# Sheet1.net
KiCad netlist of a schematic drawn in Altium Designer
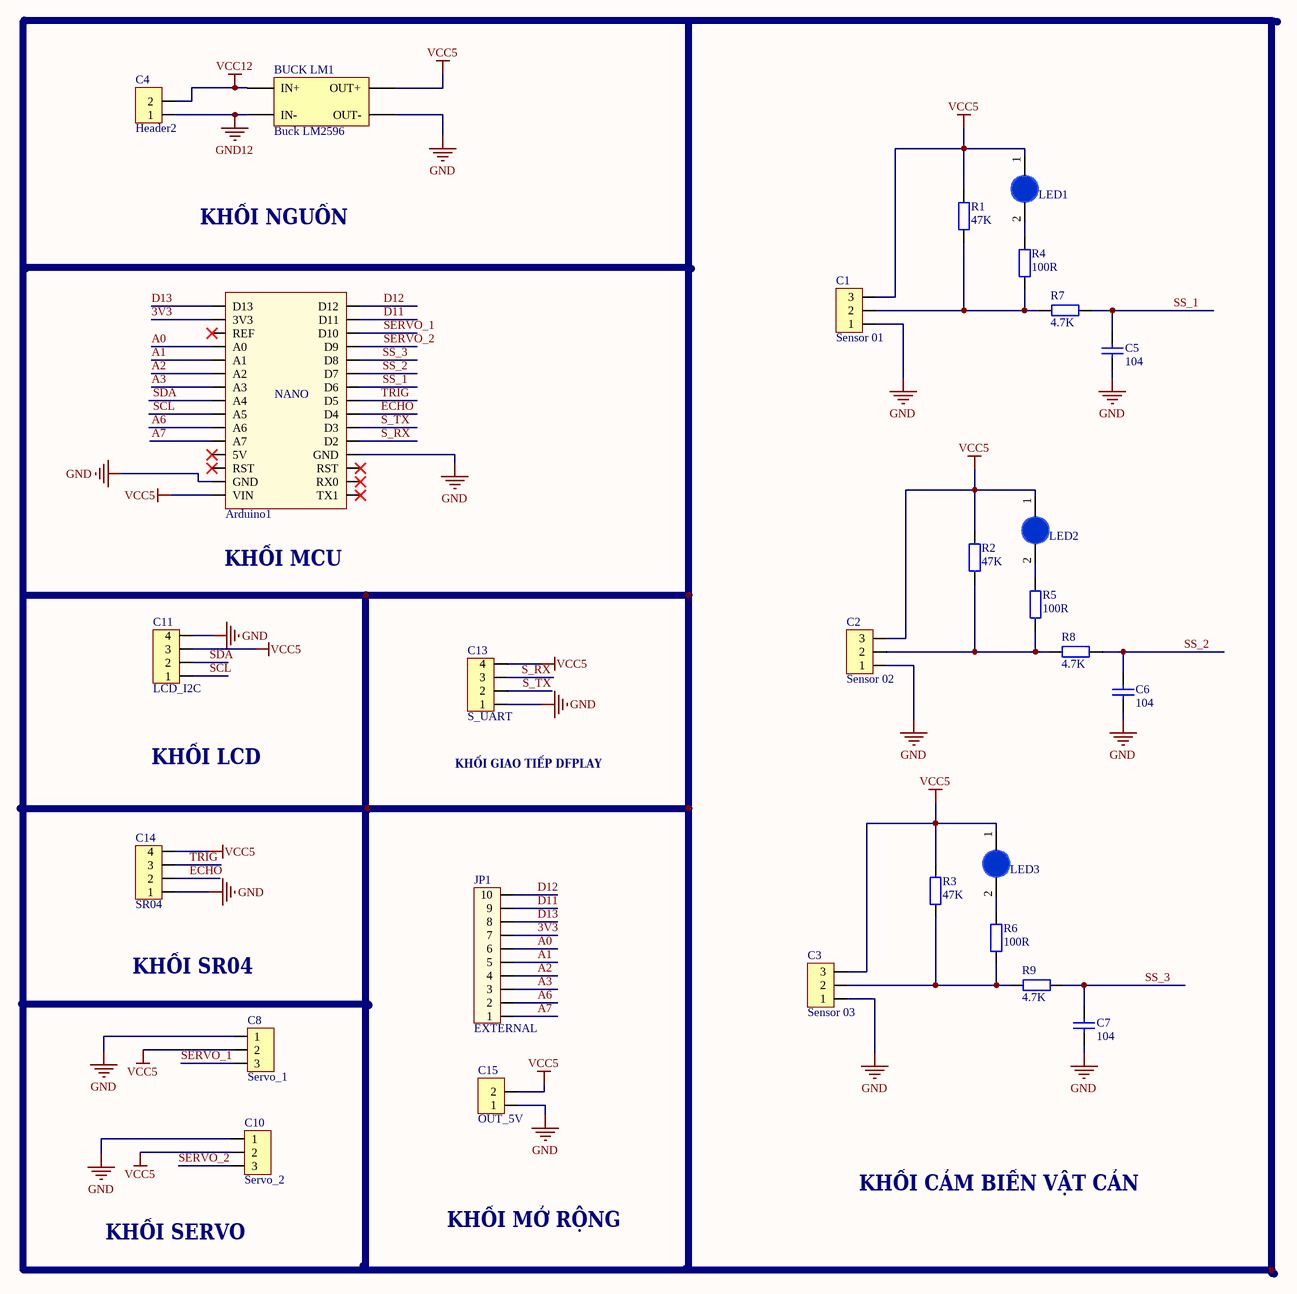
[diagram p0: Sheet1.SchDoc]

(export (version "E")
  (design (tool "Eeschema 10.0.6"))
  (components
    (comp (ref "Arduino1")
      (value "Arduino Nano")
      (footprint "Arduino Nano")
      (description "Arduino NANO")
      (libsource (lib "myLib_v1") (part "Arduino Nano"))
    )
    (comp (ref "BUCK LM1")
      (value "Buck LM2596")
      (footprint "BUCK LM2596")
      (libsource (lib "myLib_v1") (part "Buck LM2596"))
    )
    (comp (ref "C1")
      (value "Sensor 01")
      (footprint "Header3")
      (description "Header IDC, 3 x 1 Pin Vertical 2.54mm Pitch (Non-Boxed, Male)")
      (fields
        (field (name "MANUFACTURER") "Würth Elektronik eiSos GmbH")
        (field (name "PARTNO") "613002143121")
        (field (name "CREATED BY") "Karrer Zheng")
      )
      (libsource (lib "") (part "Header3_1"))
    )
    (comp (ref "C2")
      (value "Sensor 02")
      (footprint "Header3")
      (description "Header IDC, 3 x 1 Pin Vertical 2.54mm Pitch (Non-Boxed, Male)")
      (fields
        (field (name "MANUFACTURER") "Würth Elektronik eiSos GmbH")
        (field (name "PARTNO") "613002143121")
        (field (name "CREATED BY") "Karrer Zheng")
      )
      (libsource (lib "") (part "Header3_1"))
    )
    (comp (ref "C3")
      (value "Sensor 03")
      (footprint "Header3")
      (description "Header IDC, 3 x 1 Pin Vertical 2.54mm Pitch (Non-Boxed, Male)")
      (fields
        (field (name "MANUFACTURER") "Würth Elektronik eiSos GmbH")
        (field (name "PARTNO") "613002143121")
        (field (name "CREATED BY") "Karrer Zheng")
      )
      (libsource (lib "") (part "Header3_1"))
    )
    (comp (ref "C4")
      (value "Header2")
      (footprint "Header2")
      (description "Header IDC, 2 x 1 Pin Vertical 2.54mm Pitch (Non-Boxed, Male)")
      (fields
        (field (name "MANUFACTURER") "Würth Elektronik eiSos GmbH")
        (field (name "PARTNO") "613002143121")
        (field (name "CREATED BY") "Karrer Zheng")
      )
      (libsource (lib "myLib_v1") (part "Header2"))
    )
    (comp (ref "C5")
      (value "104")
      (footprint "tu gom")
      (description "Cắm")
      (libsource (lib "Altium_Lib_by_KhueNguyenCreator") (part "Tu gom 104 50V"))
    )
    (comp (ref "C6")
      (value "104")
      (footprint "tu gom")
      (description "Cắm")
      (libsource (lib "Altium_Lib_by_KhueNguyenCreator") (part "Tu gom 104 50V"))
    )
    (comp (ref "C7")
      (value "104")
      (footprint "tu gom")
      (description "Cắm")
      (libsource (lib "Altium_Lib_by_KhueNguyenCreator") (part "Tu gom 104 50V"))
    )
    (comp (ref "C8")
      (value "Servo_1")
      (footprint "Header3")
      (description "Header IDC, 3 x 1 Pin Vertical 2.54mm Pitch (Non-Boxed, Male)")
      (fields
        (field (name "MANUFACTURER") "Würth Elektronik eiSos GmbH")
        (field (name "PARTNO") "613002143121")
        (field (name "CREATED BY") "Karrer Zheng")
      )
      (libsource (lib "myLib_v1") (part "Header3"))
    )
    (comp (ref "C10")
      (value "Servo_2")
      (footprint "Header3")
      (description "Header IDC, 3 x 1 Pin Vertical 2.54mm Pitch (Non-Boxed, Male)")
      (fields
        (field (name "MANUFACTURER") "Würth Elektronik eiSos GmbH")
        (field (name "PARTNO") "613002143121")
        (field (name "CREATED BY") "Karrer Zheng")
      )
      (libsource (lib "myLib_v1") (part "Header3"))
    )
    (comp (ref "C11")
      (value "LCD_I2C")
      (footprint "Header4")
      (description "Header IDC, 4 x 1 Pin Vertical 2.54mm Pitch (Non-Boxed, Male)")
      (fields
        (field (name "MANUFACTURER") "Würth Elektronik eiSos GmbH")
        (field (name "PARTNO") "613002143121")
        (field (name "CREATED BY") "Karrer Zheng")
      )
      (libsource (lib "myLib_v1") (part "Header4"))
    )
    (comp (ref "C13")
      (value "S_UART")
      (footprint "Header4")
      (description "Header IDC, 4 x 1 Pin Vertical 2.54mm Pitch (Non-Boxed, Male)")
      (fields
        (field (name "MANUFACTURER") "Würth Elektronik eiSos GmbH")
        (field (name "PARTNO") "613002143121")
        (field (name "CREATED BY") "Karrer Zheng")
      )
      (libsource (lib "myLib_v1") (part "Header4"))
    )
    (comp (ref "C14")
      (value "SR04")
      (footprint "Header4")
      (description "Header IDC, 4 x 1 Pin Vertical 2.54mm Pitch (Non-Boxed, Male)")
      (fields
        (field (name "MANUFACTURER") "Würth Elektronik eiSos GmbH")
        (field (name "PARTNO") "613002143121")
        (field (name "CREATED BY") "Karrer Zheng")
      )
      (libsource (lib "myLib_v1") (part "Header4"))
    )
    (comp (ref "C15")
      (value "OUT_5V")
      (footprint "Header2")
      (description "Header IDC, 2 x 1 Pin Vertical 2.54mm Pitch (Non-Boxed, Male)")
      (fields
        (field (name "MANUFACTURER") "Würth Elektronik eiSos GmbH")
        (field (name "PARTNO") "613002143121")
        (field (name "CREATED BY") "Karrer Zheng")
      )
      (libsource (lib "myLib_v1") (part "Header2"))
    )
    (comp (ref "JP1")
      (value "EXTERNAL")
      (footprint "Header10")
      (description "Connector 10")
      (libsource (lib "myLib_v1") (part "Header10"))
    )
    (comp (ref "LED1")
      (value "LED 3mm")
      (footprint "LED-3MM-BLUE")
      (description "Cắm")
      (libsource (lib "myLib_v1") (part "LED 3mm Xanh Duong"))
    )
    (comp (ref "LED2")
      (value "LED 3mm")
      (footprint "LED-3MM-BLUE")
      (description "Cắm")
      (libsource (lib "myLib_v1") (part "LED 3mm Xanh Duong"))
    )
    (comp (ref "LED3")
      (value "LED 3mm")
      (footprint "LED-3MM-BLUE")
      (description "Cắm")
      (libsource (lib "myLib_v1") (part "LED 3mm Xanh Duong"))
    )
    (comp (ref "R1")
      (value "47K")
      (footprint "R1/4W")
      (description "Resistor 1/4W")
      (libsource (lib "myLib_v1") (part "R1/4W"))
    )
    (comp (ref "R2")
      (value "47K")
      (footprint "R1/4W")
      (description "Resistor 1/4W")
      (libsource (lib "myLib_v1") (part "R1/4W"))
    )
    (comp (ref "R3")
      (value "47K")
      (footprint "R1/4W")
      (description "Resistor 1/4W")
      (libsource (lib "myLib_v1") (part "R1/4W"))
    )
    (comp (ref "R4")
      (value "100R")
      (footprint "R1/4W")
      (description "Resistor 1/4W")
      (libsource (lib "myLib_v1") (part "R1/4W"))
    )
    (comp (ref "R5")
      (value "100R")
      (footprint "R1/4W")
      (description "Resistor 1/4W")
      (libsource (lib "myLib_v1") (part "R1/4W"))
    )
    (comp (ref "R6")
      (value "100R")
      (footprint "R1/4W")
      (description "Resistor 1/4W")
      (libsource (lib "myLib_v1") (part "R1/4W"))
    )
    (comp (ref "R7")
      (value "4.7K")
      (footprint "R1/4W")
      (description "Resistor 1/4W")
      (libsource (lib "myLib_v1") (part "R1/4W"))
    )
    (comp (ref "R8")
      (value "4.7K")
      (footprint "R1/4W")
      (description "Resistor 1/4W")
      (libsource (lib "myLib_v1") (part "R1/4W"))
    )
    (comp (ref "R9")
      (value "4.7K")
      (footprint "R1/4W")
      (description "Resistor 1/4W")
      (libsource (lib "myLib_v1") (part "R1/4W"))
    )
  )
  (nets
    (net (code "1") (name "/3V3") (class "Default")
      (node (ref "Arduino1") (pin "3V3") (pinfunction "3V3_3V3") (pintype "passive"))
      (node (ref "JP1") (pin "7") (pinfunction "7_7") (pintype "passive"))
    )
    (net (code "2") (name "/A0") (class "Default")
      (node (ref "Arduino1") (pin "A0") (pinfunction "A0_A0") (pintype "passive"))
      (node (ref "JP1") (pin "6") (pinfunction "6_6") (pintype "passive"))
    )
    (net (code "3") (name "/A1") (class "Default")
      (node (ref "Arduino1") (pin "A1") (pinfunction "A1_A1") (pintype "passive"))
      (node (ref "JP1") (pin "5") (pinfunction "5_5") (pintype "passive"))
    )
    (net (code "4") (name "/A2") (class "Default")
      (node (ref "Arduino1") (pin "A2") (pinfunction "A2_A2") (pintype "passive"))
      (node (ref "JP1") (pin "4") (pinfunction "4_4") (pintype "passive"))
    )
    (net (code "5") (name "/A3") (class "Default")
      (node (ref "Arduino1") (pin "A3") (pinfunction "A3_A3") (pintype "passive"))
      (node (ref "JP1") (pin "3") (pinfunction "3_3") (pintype "passive"))
    )
    (net (code "6") (name "/A6") (class "Default")
      (node (ref "Arduino1") (pin "A6") (pinfunction "A6_A6") (pintype "passive"))
      (node (ref "JP1") (pin "2") (pinfunction "2_2") (pintype "passive"))
    )
    (net (code "7") (name "/A7") (class "Default")
      (node (ref "Arduino1") (pin "A7") (pinfunction "A7_A7") (pintype "passive"))
      (node (ref "JP1") (pin "1") (pinfunction "1_1") (pintype "passive"))
    )
    (net (code "8") (name "/D11") (class "Default")
      (node (ref "Arduino1") (pin "D11") (pinfunction "D11_D11") (pintype "passive"))
      (node (ref "JP1") (pin "9") (pinfunction "9_9") (pintype "passive"))
    )
    (net (code "9") (name "/D12") (class "Default")
      (node (ref "Arduino1") (pin "D12") (pinfunction "D12_D12") (pintype "passive"))
      (node (ref "JP1") (pin "10") (pinfunction "10_10") (pintype "passive"))
    )
    (net (code "10") (name "/D13") (class "Default")
      (node (ref "Arduino1") (pin "D13") (pinfunction "D13_D13") (pintype "passive"))
      (node (ref "JP1") (pin "8") (pinfunction "8_8") (pintype "passive"))
    )
    (net (code "11") (name "/ECHO") (class "Default")
      (node (ref "Arduino1") (pin "D4") (pinfunction "D4_D4") (pintype "passive"))
      (node (ref "C14") (pin "2") (pinfunction "2_2") (pintype "passive"))
    )
    (net (code "12") (name "/SCL") (class "Default")
      (node (ref "Arduino1") (pin "A5") (pinfunction "A5_A5") (pintype "passive"))
      (node (ref "C11") (pin "1") (pinfunction "1_1") (pintype "passive"))
    )
    (net (code "13") (name "/SDA") (class "Default")
      (node (ref "Arduino1") (pin "A4") (pinfunction "A4_A4") (pintype "passive"))
      (node (ref "C11") (pin "2") (pinfunction "2_2") (pintype "passive"))
    )
    (net (code "14") (name "/SERVO_1") (class "Default")
      (node (ref "Arduino1") (pin "D10") (pinfunction "D10_D10") (pintype "passive"))
      (node (ref "C8") (pin "3") (pinfunction "3_3") (pintype "passive"))
    )
    (net (code "15") (name "/SERVO_2") (class "Default")
      (node (ref "Arduino1") (pin "D9") (pinfunction "D9_D9") (pintype "passive"))
      (node (ref "C10") (pin "3") (pinfunction "3_3") (pintype "passive"))
    )
    (net (code "16") (name "/SS_1") (class "Default")
      (node (ref "Arduino1") (pin "D6") (pinfunction "D6_D6") (pintype "passive"))
      (node (ref "C5") (pin "1") (pinfunction "1_1") (pintype "passive"))
      (node (ref "R7") (pin "1") (pinfunction "1_1") (pintype "passive"))
    )
    (net (code "17") (name "/SS_2") (class "Default")
      (node (ref "Arduino1") (pin "D7") (pinfunction "D7_D7") (pintype "passive"))
      (node (ref "C6") (pin "1") (pinfunction "1_1") (pintype "passive"))
      (node (ref "R8") (pin "1") (pinfunction "1_1") (pintype "passive"))
    )
    (net (code "18") (name "/SS_3") (class "Default")
      (node (ref "Arduino1") (pin "D8") (pinfunction "D8_D8") (pintype "passive"))
      (node (ref "C7") (pin "1") (pinfunction "1_1") (pintype "passive"))
      (node (ref "R9") (pin "1") (pinfunction "1_1") (pintype "passive"))
    )
    (net (code "19") (name "/S_RX") (class "Default")
      (node (ref "Arduino1") (pin "D2") (pinfunction "D2_D2") (pintype "passive"))
      (node (ref "C13") (pin "3") (pinfunction "3_3") (pintype "passive"))
    )
    (net (code "20") (name "/S_TX") (class "Default")
      (node (ref "Arduino1") (pin "D3") (pinfunction "D3_D3") (pintype "passive"))
      (node (ref "C13") (pin "2") (pinfunction "2_2") (pintype "passive"))
    )
    (net (code "21") (name "/TRIG") (class "Default")
      (node (ref "Arduino1") (pin "D5") (pinfunction "D5_D5") (pintype "passive"))
      (node (ref "C14") (pin "3") (pinfunction "3_3") (pintype "passive"))
    )
    (net (code "22") (name "GND") (class "Default")
      (node (ref "Arduino1") (pin "GND") (pinfunction "GND_GND") (pintype "passive"))
      (node (ref "BUCK LM1") (pin "3") (pinfunction "OUT-_3") (pintype "passive"))
      (node (ref "C1") (pin "1") (pinfunction "1_1") (pintype "passive"))
      (node (ref "C10") (pin "1") (pinfunction "1_1") (pintype "passive"))
      (node (ref "C11") (pin "4") (pinfunction "4_4") (pintype "passive"))
      (node (ref "C13") (pin "1") (pinfunction "1_1") (pintype "passive"))
      (node (ref "C14") (pin "1") (pinfunction "1_1") (pintype "passive"))
      (node (ref "C15") (pin "1") (pinfunction "1_1") (pintype "passive"))
      (node (ref "C2") (pin "1") (pinfunction "1_1") (pintype "passive"))
      (node (ref "C3") (pin "1") (pinfunction "1_1") (pintype "passive"))
      (node (ref "C5") (pin "2") (pinfunction "2_2") (pintype "passive"))
      (node (ref "C6") (pin "2") (pinfunction "2_2") (pintype "passive"))
      (node (ref "C7") (pin "2") (pinfunction "2_2") (pintype "passive"))
      (node (ref "C8") (pin "1") (pinfunction "1_1") (pintype "passive"))
    )
    (net (code "23") (name "GND12") (class "Default")
      (node (ref "BUCK LM1") (pin "2") (pinfunction "IN-_2") (pintype "passive"))
      (node (ref "C4") (pin "1") (pinfunction "1_1") (pintype "passive"))
    )
    (net (code "24") (name "Net-(C1-Pad2)") (class "Default")
      (node (ref "C1") (pin "2") (pinfunction "2_2") (pintype "passive"))
      (node (ref "R1") (pin "1") (pinfunction "1_1") (pintype "passive"))
      (node (ref "R4") (pin "1") (pinfunction "1_1") (pintype "passive"))
      (node (ref "R7") (pin "2") (pinfunction "2_2") (pintype "passive"))
    )
    (net (code "25") (name "Net-(C2-Pad2)") (class "Default")
      (node (ref "C2") (pin "2") (pinfunction "2_2") (pintype "passive"))
      (node (ref "R2") (pin "1") (pinfunction "1_1") (pintype "passive"))
      (node (ref "R5") (pin "1") (pinfunction "1_1") (pintype "passive"))
      (node (ref "R8") (pin "2") (pinfunction "2_2") (pintype "passive"))
    )
    (net (code "26") (name "Net-(C3-Pad2)") (class "Default")
      (node (ref "C3") (pin "2") (pinfunction "2_2") (pintype "passive"))
      (node (ref "R3") (pin "1") (pinfunction "1_1") (pintype "passive"))
      (node (ref "R6") (pin "1") (pinfunction "1_1") (pintype "passive"))
      (node (ref "R9") (pin "2") (pinfunction "2_2") (pintype "passive"))
    )
    (net (code "27") (name "Net-(LED1-K)") (class "Default")
      (node (ref "LED1") (pin "2") (pinfunction "K_2") (pintype "passive"))
      (node (ref "R4") (pin "2") (pinfunction "2_2") (pintype "passive"))
    )
    (net (code "28") (name "Net-(LED2-K)") (class "Default")
      (node (ref "LED2") (pin "2") (pinfunction "K_2") (pintype "passive"))
      (node (ref "R5") (pin "2") (pinfunction "2_2") (pintype "passive"))
    )
    (net (code "29") (name "Net-(LED3-K)") (class "Default")
      (node (ref "LED3") (pin "2") (pinfunction "K_2") (pintype "passive"))
      (node (ref "R6") (pin "2") (pinfunction "2_2") (pintype "passive"))
    )
    (net (code "30") (name "VCC5") (class "Default")
      (node (ref "Arduino1") (pin "VIN") (pinfunction "VIN_VIN") (pintype "passive"))
      (node (ref "BUCK LM1") (pin "4") (pinfunction "OUT+_4") (pintype "passive"))
      (node (ref "C1") (pin "3") (pinfunction "3_3") (pintype "passive"))
      (node (ref "C10") (pin "2") (pinfunction "2_2") (pintype "passive"))
      (node (ref "C11") (pin "3") (pinfunction "3_3") (pintype "passive"))
      (node (ref "C13") (pin "4") (pinfunction "4_4") (pintype "passive"))
      (node (ref "C14") (pin "4") (pinfunction "4_4") (pintype "passive"))
      (node (ref "C15") (pin "2") (pinfunction "2_2") (pintype "passive"))
      (node (ref "C2") (pin "3") (pinfunction "3_3") (pintype "passive"))
      (node (ref "C3") (pin "3") (pinfunction "3_3") (pintype "passive"))
      (node (ref "C8") (pin "2") (pinfunction "2_2") (pintype "passive"))
      (node (ref "LED1") (pin "1") (pinfunction "A_1") (pintype "passive"))
      (node (ref "LED2") (pin "1") (pinfunction "A_1") (pintype "passive"))
      (node (ref "LED3") (pin "1") (pinfunction "A_1") (pintype "passive"))
      (node (ref "R1") (pin "2") (pinfunction "2_2") (pintype "passive"))
      (node (ref "R2") (pin "2") (pinfunction "2_2") (pintype "passive"))
      (node (ref "R3") (pin "2") (pinfunction "2_2") (pintype "passive"))
    )
    (net (code "31") (name "VCC12") (class "Default")
      (node (ref "BUCK LM1") (pin "1") (pinfunction "IN+_1") (pintype "passive"))
      (node (ref "C4") (pin "2") (pinfunction "2_2") (pintype "passive"))
    )
    (net (code "32") (name "unconnected-(Arduino1-Pad5V)") (class "Default")
      (node (ref "Arduino1") (pin "5V") (pinfunction "5V_5V") (pintype "passive+no_connect"))
    )
    (net (code "33") (name "unconnected-(Arduino1-PadREF)") (class "Default")
      (node (ref "Arduino1") (pin "REF") (pinfunction "REF_REF") (pintype "passive+no_connect"))
    )
    (net (code "34") (name "unconnected-(Arduino1-PadRST)") (class "Default")
      (node (ref "Arduino1") (pin "RST") (pinfunction "RST_RST") (pintype "passive+no_connect"))
    )
    (net (code "35") (name "unconnected-(Arduino1-PadRST)_1") (class "Default")
      (node (ref "Arduino1") (pin "RST") (pinfunction "RST_RST") (pintype "passive+no_connect"))
    )
    (net (code "36") (name "unconnected-(Arduino1-PadRX0)") (class "Default")
      (node (ref "Arduino1") (pin "RX0") (pinfunction "RX0_RX0") (pintype "passive+no_connect"))
    )
    (net (code "37") (name "unconnected-(Arduino1-PadTX1)") (class "Default")
      (node (ref "Arduino1") (pin "TX1") (pinfunction "TX1_TX1") (pintype "passive+no_connect"))
    )
  )
)
